# RemovingGround.net
KiCad netlist of a schematic drawn in EAGLE
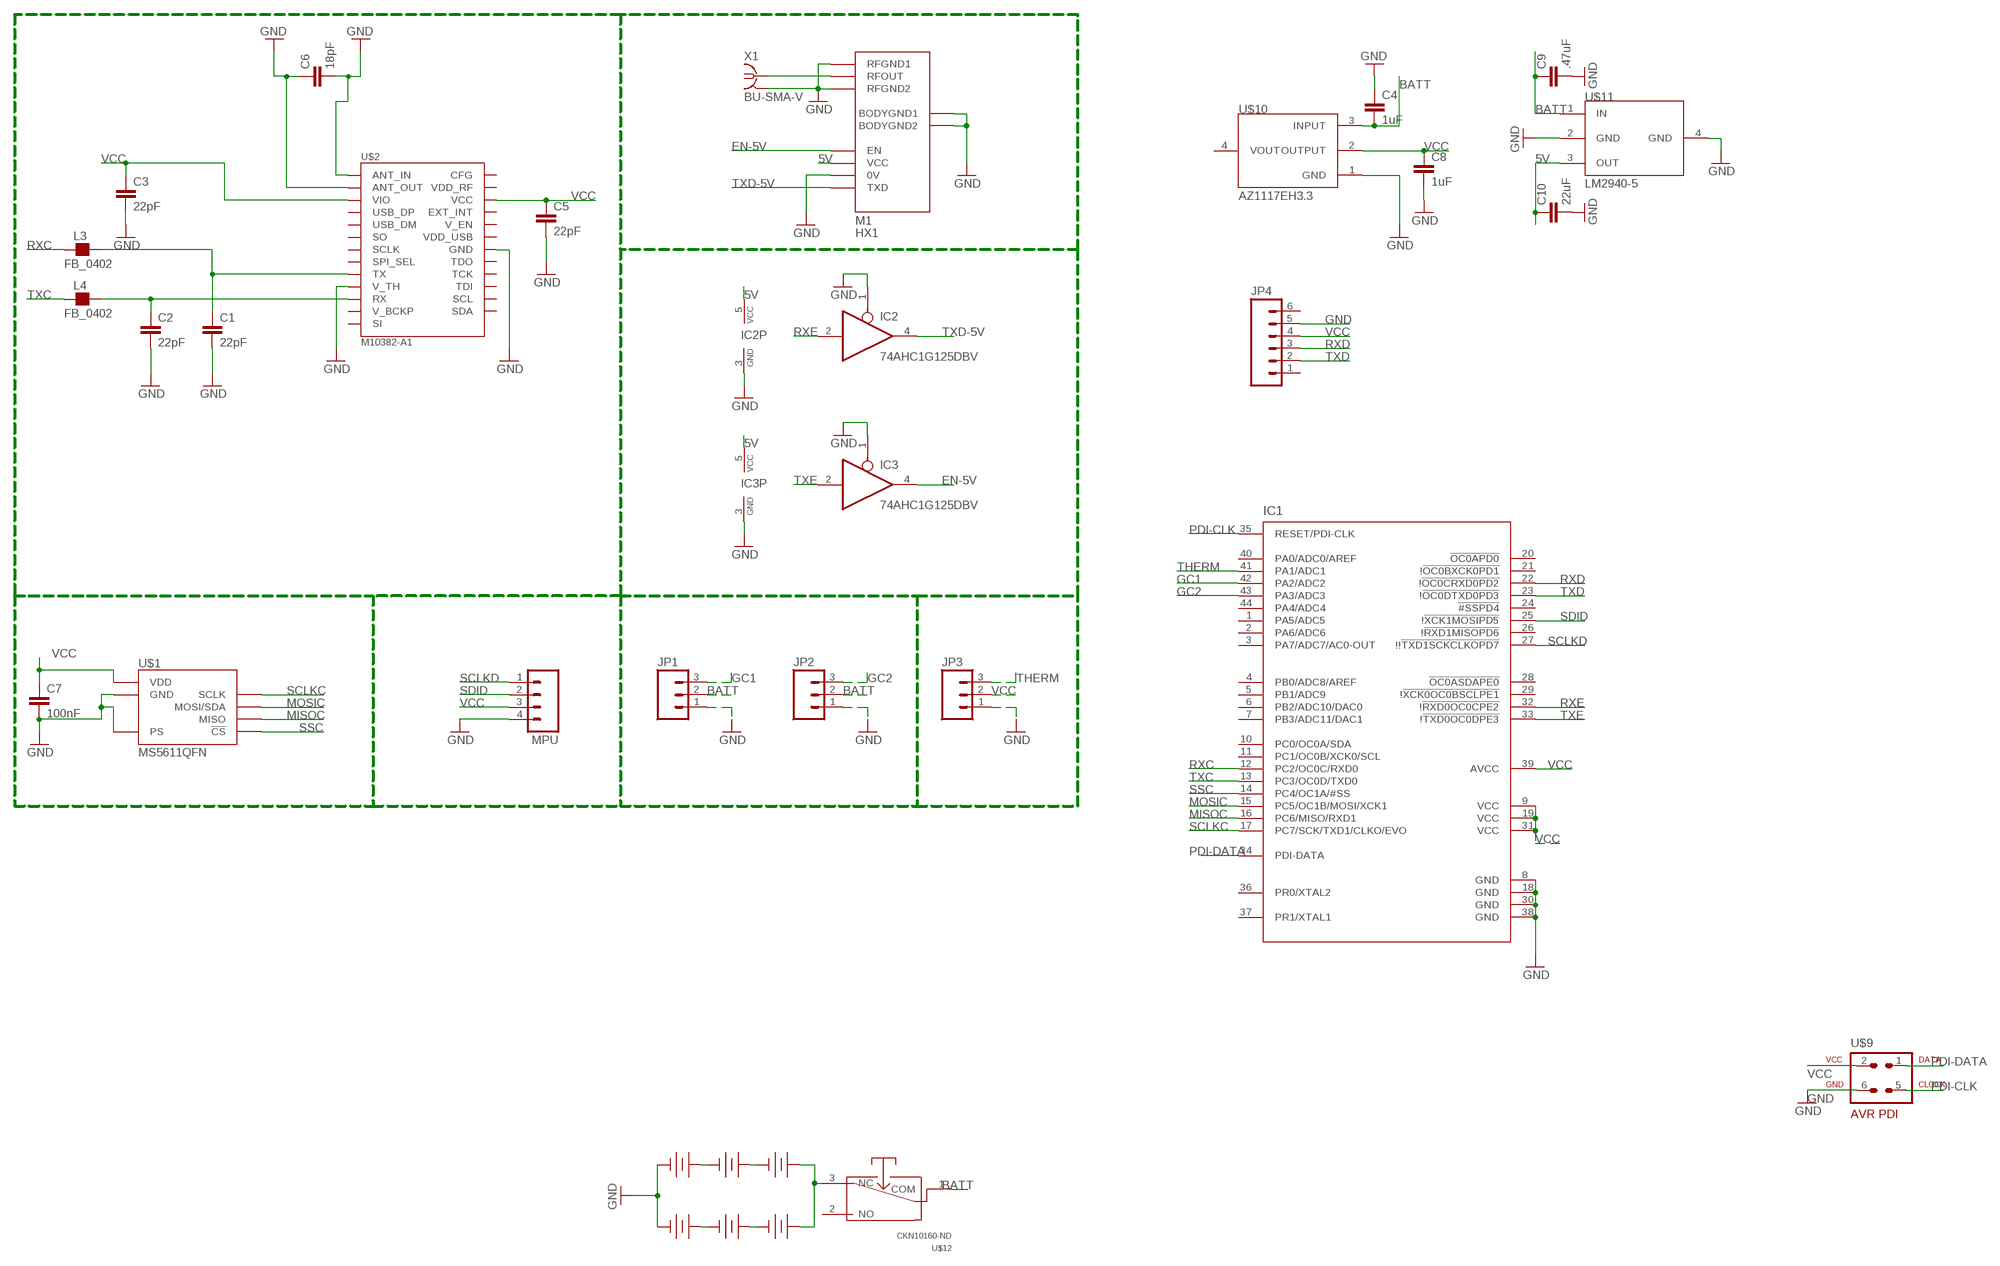
[diagram p0: schematic, sheet 1]

(export (version "E")
  (design (tool "Eeschema 10.0.6"))
  (components
    (comp (ref "C1")
      (value "22pF")
      (footprint "eagle-import:0805")
      (libsource (lib "eagle-import") (part "CAP0805"))
    )
    (comp (ref "C2")
      (value "22pF")
      (footprint "eagle-import:0805")
      (libsource (lib "eagle-import") (part "CAP0805"))
    )
    (comp (ref "C3")
      (value "22pF")
      (footprint "eagle-import:0805")
      (libsource (lib "eagle-import") (part "CAP0805"))
    )
    (comp (ref "C4")
      (value "1uF")
      (footprint "eagle-import:0603-CAP")
      (libsource (lib "eagle-import") (part "CAP0603-CAP"))
    )
    (comp (ref "C5")
      (value "22pF")
      (footprint "eagle-import:0805")
      (libsource (lib "eagle-import") (part "CAP0805"))
    )
    (comp (ref "C6")
      (value "18pF")
      (footprint "eagle-import:0805")
      (libsource (lib "eagle-import") (part "CAP0805"))
    )
    (comp (ref "C7")
      (value "100nF")
      (footprint "eagle-import:0805")
      (libsource (lib "eagle-import") (part "CAP0805"))
    )
    (comp (ref "C8")
      (value "1uF")
      (footprint "eagle-import:0603-CAP")
      (libsource (lib "eagle-import") (part "CAP0603-CAP"))
    )
    (comp (ref "C9")
      (value ".47uF")
      (footprint "eagle-import:0603-CAP")
      (libsource (lib "eagle-import") (part "CAP0603-CAP"))
    )
    (comp (ref "C10")
      (value "22uF")
      (footprint "eagle-import:0603-CAP")
      (libsource (lib "eagle-import") (part "CAP0603-CAP"))
    )
    (comp (ref "IC1")
      (value "AT-XMEGA-XXA4-AU")
      (footprint "eagle-import:QFP80P1200X1200X120-44N")
      (libsource (lib "eagle-import") (part "AT-XMEGA-XXA4-AU"))
    )
    (comp (ref "IC2")
      (value "74AHC1G125DBV")
      (footprint "eagle-import:SOT23-5")
      (libsource (lib "eagle-import") (part "741G125DBVAHC"))
    )
    (comp (ref "IC3")
      (value "74AHC1G125DBV")
      (footprint "eagle-import:SOT23-5")
      (libsource (lib "eagle-import") (part "741G125DBVAHC"))
    )
    (comp (ref "JP1")
      (value "M03JST-PTH")
      (footprint "eagle-import:JST-3-PTH")
      (libsource (lib "eagle-import") (part "M03JST-PTH"))
    )
    (comp (ref "JP2")
      (value "M03JST-PTH")
      (footprint "eagle-import:JST-3-PTH")
      (libsource (lib "eagle-import") (part "M03JST-PTH"))
    )
    (comp (ref "JP3")
      (value "M03JST-PTH")
      (footprint "eagle-import:JST-3-PTH")
      (libsource (lib "eagle-import") (part "M03JST-PTH"))
    )
    (comp (ref "JP4")
      (value "M06POLAR")
      (footprint "eagle-import:MOLEX-1X6")
      (libsource (lib "eagle-import") (part "M06POLAR"))
    )
    (comp (ref "L3")
      (value "FB_0402")
      (footprint "eagle-import:L0402")
      (libsource (lib "eagle-import") (part "FB_0402"))
    )
    (comp (ref "L4")
      (value "FB_0402")
      (footprint "eagle-import:L0402")
      (libsource (lib "eagle-import") (part "FB_0402"))
    )
    (comp (ref "M1")
      (value "HX1")
      (footprint "eagle-import:HX1")
      (libsource (lib "eagle-import") (part "HX1"))
    )
    (comp (ref "MPU")
      (value "M04")
      (footprint "eagle-import:04P")
      (libsource (lib "eagle-import") (part "M04"))
    )
    (comp (ref "U$1")
      (value "MS5611QFN")
      (footprint "eagle-import:MS5611-01BA01")
      (libsource (lib "eagle-import") (part "MS5611QFN"))
    )
    (comp (ref "U$2")
      (value "M10382-A1")
      (footprint "eagle-import:M10382-A1")
      (libsource (lib "eagle-import") (part "M10382-A1"))
    )
    (comp (ref "U$3")
      (value "123_BATTERY_HOLDERCR-123-A")
      (footprint "eagle-import:CR-123-A_HOLDER")
      (libsource (lib "eagle-import") (part "123_BATTERY_HOLDERCR-123-A"))
    )
    (comp (ref "U$4")
      (value "123_BATTERY_HOLDERCR-123-A")
      (footprint "eagle-import:CR-123-A_HOLDER")
      (libsource (lib "eagle-import") (part "123_BATTERY_HOLDERCR-123-A"))
    )
    (comp (ref "U$5")
      (value "123_BATTERY_HOLDERCR-123-A")
      (footprint "eagle-import:CR-123-A_HOLDER")
      (libsource (lib "eagle-import") (part "123_BATTERY_HOLDERCR-123-A"))
    )
    (comp (ref "U$6")
      (value "123_BATTERY_HOLDERCR-123-A")
      (footprint "eagle-import:CR-123-A_HOLDER")
      (libsource (lib "eagle-import") (part "123_BATTERY_HOLDERCR-123-A"))
    )
    (comp (ref "U$7")
      (value "123_BATTERY_HOLDERCR-123-A")
      (footprint "eagle-import:CR-123-A_HOLDER")
      (libsource (lib "eagle-import") (part "123_BATTERY_HOLDERCR-123-A"))
    )
    (comp (ref "U$8")
      (value "123_BATTERY_HOLDERCR-123-A")
      (footprint "eagle-import:CR-123-A_HOLDER")
      (libsource (lib "eagle-import") (part "123_BATTERY_HOLDERCR-123-A"))
    )
    (comp (ref "U$9")
      (value "AVR-PDIVERT")
      (footprint "eagle-import:AVR-ISP-6")
      (libsource (lib "eagle-import") (part "AVR-PDIVERT"))
    )
    (comp (ref "U$10")
      (value "AZ1117EH3.3")
      (footprint "eagle-import:SOT-223")
      (libsource (lib "eagle-import") (part "AZ1117EH3.3"))
    )
    (comp (ref "U$11")
      (value "LM2940-5")
      (footprint "eagle-import:SOT-223")
      (libsource (lib "eagle-import") (part "LM2940-5"))
    )
    (comp (ref "U$12")
      (value "CKN10160-ND")
      (footprint "eagle-import:ZMCHFL3R")
      (libsource (lib "eagle-import") (part "CKN10160-ND"))
    )
    (comp (ref "X1")
      (value "BU-SMA-V")
      (footprint "eagle-import:BU-SMA-V")
      (libsource (lib "eagle-import") (part "BU-SMA-V"))
    )
  )
  (nets
    (net (code "1") (name "/5V") (class "Default")
      (node (ref "C10") (pin "1") (pinfunction "1_1") (pintype "passive"))
      (node (ref "IC2") (pin "5") (pinfunction "VCC_5") (pintype "power_in"))
      (node (ref "IC3") (pin "5") (pinfunction "VCC_5") (pintype "power_in"))
      (node (ref "M1") (pin "VCC") (pinfunction "VCC_VCC") (pintype "bidirectional"))
      (node (ref "U$11") (pin "3") (pinfunction "OUT_3") (pintype "bidirectional"))
    )
    (net (code "2") (name "/BATT") (class "Default")
      (node (ref "C4") (pin "2") (pinfunction "2_2") (pintype "passive"))
      (node (ref "C9") (pin "1") (pinfunction "1_1") (pintype "passive"))
      (node (ref "JP1") (pin "2") (pinfunction "2_2") (pintype "passive"))
      (node (ref "JP2") (pin "2") (pinfunction "2_2") (pintype "passive"))
      (node (ref "U$10") (pin "3") (pinfunction "INPUT_3") (pintype "bidirectional"))
      (node (ref "U$11") (pin "1") (pinfunction "IN_1") (pintype "bidirectional"))
      (node (ref "U$12") (pin "1") (pinfunction "COM_1") (pintype "bidirectional"))
    )
    (net (code "3") (name "/EN-5V") (class "Default")
      (node (ref "IC3") (pin "4") (pinfunction "O_4") (pintype "tri_state"))
      (node (ref "M1") (pin "EN") (pinfunction "EN_EN") (pintype "bidirectional"))
    )
    (net (code "4") (name "/GC1") (class "Default")
      (node (ref "IC1") (pin "42") (pinfunction "PA2/ADC2_42") (pintype "bidirectional"))
      (node (ref "JP1") (pin "3") (pinfunction "3_3") (pintype "passive"))
    )
    (net (code "5") (name "/GC2") (class "Default")
      (node (ref "IC1") (pin "43") (pinfunction "PA3/ADC3_43") (pintype "bidirectional"))
      (node (ref "JP2") (pin "3") (pinfunction "3_3") (pintype "passive"))
    )
    (net (code "6") (name "/MISOC") (class "Default")
      (node (ref "IC1") (pin "16") (pinfunction "PC6/MISO/RXD1_16") (pintype "bidirectional"))
      (node (ref "U$1") (pin "6") (pinfunction "MISO_6") (pintype "bidirectional"))
    )
    (net (code "7") (name "/MOSIC") (class "Default")
      (node (ref "IC1") (pin "15") (pinfunction "PC5/OC1B/MOSI/XCK1_15") (pintype "bidirectional"))
      (node (ref "U$1") (pin "7") (pinfunction "MOSI/SDA_7") (pintype "bidirectional"))
    )
    (net (code "8") (name "/PDI-CLK") (class "Default")
      (node (ref "IC1") (pin "35") (pinfunction "RESET/PDI-CLK_35") (pintype "input"))
      (node (ref "U$9") (pin "5") (pinfunction "5_5") (pintype "passive"))
    )
    (net (code "9") (name "/PDI-DATA") (class "Default")
      (node (ref "IC1") (pin "34") (pinfunction "PDI-DATA_34") (pintype "bidirectional"))
      (node (ref "U$9") (pin "1") (pinfunction "1_1") (pintype "passive"))
    )
    (net (code "10") (name "/RXC") (class "Default")
      (node (ref "IC1") (pin "12") (pinfunction "PC2/OC0C/RXD0_12") (pintype "bidirectional"))
      (node (ref "L3") (pin "1") (pinfunction "1_1") (pintype "passive"))
    )
    (net (code "11") (name "/RXD") (class "Default")
      (node (ref "IC1") (pin "22") (pinfunction "~OC0CRXD0PD2_22") (pintype "bidirectional"))
      (node (ref "JP4") (pin "3") (pinfunction "3_3") (pintype "passive"))
    )
    (net (code "12") (name "/RXE") (class "Default")
      (node (ref "IC1") (pin "32") (pinfunction "~RXD0OC0CPE2_32") (pintype "bidirectional"))
      (node (ref "IC2") (pin "2") (pinfunction "I_2") (pintype "input"))
    )
    (net (code "13") (name "/SCLKC") (class "Default")
      (node (ref "IC1") (pin "17") (pinfunction "PC7/SCK/TXD1/CLKO/EVO_17") (pintype "bidirectional"))
      (node (ref "U$1") (pin "8") (pinfunction "SCLK_8") (pintype "bidirectional"))
    )
    (net (code "14") (name "/SCLKD") (class "Default")
      (node (ref "IC1") (pin "27") (pinfunction "~~{TXD1SCKCLKOPD7}_27") (pintype "bidirectional"))
      (node (ref "MPU") (pin "1") (pinfunction "1_1") (pintype "passive"))
    )
    (net (code "15") (name "/SDID") (class "Default")
      (node (ref "IC1") (pin "25") (pinfunction "~XCK1MOSIPD5_25") (pintype "bidirectional"))
      (node (ref "MPU") (pin "2") (pinfunction "2_2") (pintype "passive"))
    )
    (net (code "16") (name "/SSC") (class "Default")
      (node (ref "IC1") (pin "14") (pinfunction "PC4/OC1A/#SS_14") (pintype "bidirectional"))
      (node (ref "U$1") (pin "4") (pinfunction "~{CS}_4") (pintype "bidirectional"))
      (node (ref "U$1") (pin "5") (pinfunction "~{CS}_5") (pintype "bidirectional"))
    )
    (net (code "17") (name "/THERM") (class "Default")
      (node (ref "IC1") (pin "41") (pinfunction "PA1/ADC1_41") (pintype "bidirectional"))
      (node (ref "JP3") (pin "3") (pinfunction "3_3") (pintype "passive"))
    )
    (net (code "18") (name "/TXC") (class "Default")
      (node (ref "IC1") (pin "13") (pinfunction "PC3/OC0D/TXD0_13") (pintype "bidirectional"))
      (node (ref "L4") (pin "1") (pinfunction "1_1") (pintype "passive"))
    )
    (net (code "19") (name "/TXD") (class "Default")
      (node (ref "IC1") (pin "23") (pinfunction "~OC0DTXD0PD3_23") (pintype "bidirectional"))
      (node (ref "JP4") (pin "2") (pinfunction "2_2") (pintype "passive"))
    )
    (net (code "20") (name "/TXD-5V") (class "Default")
      (node (ref "IC2") (pin "4") (pinfunction "O_4") (pintype "tri_state"))
      (node (ref "M1") (pin "TXD") (pinfunction "TXD_TXD") (pintype "bidirectional"))
    )
    (net (code "21") (name "/TXE") (class "Default")
      (node (ref "IC1") (pin "33") (pinfunction "~TXD0OC0DPE3_33") (pintype "bidirectional"))
      (node (ref "IC3") (pin "2") (pinfunction "I_2") (pintype "input"))
    )
    (net (code "22") (name "/VCC") (class "Default")
      (node (ref "C3") (pin "1") (pinfunction "1_1") (pintype "passive"))
      (node (ref "C5") (pin "1") (pinfunction "1_1") (pintype "passive"))
      (node (ref "C7") (pin "1") (pinfunction "1_1") (pintype "passive"))
      (node (ref "C8") (pin "1") (pinfunction "1_1") (pintype "passive"))
      (node (ref "IC1") (pin "19") (pinfunction "VCC_19") (pintype "power_in"))
      (node (ref "IC1") (pin "31") (pinfunction "VCC_31") (pintype "power_in"))
      (node (ref "IC1") (pin "39") (pinfunction "AVCC_39") (pintype "power_in"))
      (node (ref "IC1") (pin "9") (pinfunction "VCC_9") (pintype "power_in"))
      (node (ref "JP3") (pin "2") (pinfunction "2_2") (pintype "passive"))
      (node (ref "JP4") (pin "4") (pinfunction "4_4") (pintype "passive"))
      (node (ref "MPU") (pin "3") (pinfunction "3_3") (pintype "passive"))
      (node (ref "U$1") (pin "1") (pinfunction "VDD_1") (pintype "bidirectional"))
      (node (ref "U$10") (pin "2") (pinfunction "OUTPUT_2") (pintype "bidirectional"))
      (node (ref "U$2") (pin "27") (pinfunction "VCC_27") (pintype "bidirectional"))
      (node (ref "U$2") (pin "5") (pinfunction "VIO_5") (pintype "bidirectional"))
      (node (ref "U$9") (pin "2") (pinfunction "2_2") (pintype "passive"))
    )
    (net (code "23") (name "GND") (class "Default")
      (node (ref "C1") (pin "2") (pinfunction "2_2") (pintype "passive"))
      (node (ref "C10") (pin "2") (pinfunction "2_2") (pintype "passive"))
      (node (ref "C2") (pin "2") (pinfunction "2_2") (pintype "passive"))
      (node (ref "C3") (pin "2") (pinfunction "2_2") (pintype "passive"))
      (node (ref "C4") (pin "1") (pinfunction "1_1") (pintype "passive"))
      (node (ref "C5") (pin "2") (pinfunction "2_2") (pintype "passive"))
      (node (ref "C6") (pin "1") (pinfunction "1_1") (pintype "passive"))
      (node (ref "C6") (pin "2") (pinfunction "2_2") (pintype "passive"))
      (node (ref "C7") (pin "2") (pinfunction "2_2") (pintype "passive"))
      (node (ref "C8") (pin "2") (pinfunction "2_2") (pintype "passive"))
      (node (ref "C9") (pin "2") (pinfunction "2_2") (pintype "passive"))
      (node (ref "IC1") (pin "18") (pinfunction "GND_18") (pintype "power_in"))
      (node (ref "IC1") (pin "30") (pinfunction "GND_30") (pintype "power_in"))
      (node (ref "IC1") (pin "38") (pinfunction "GND_38") (pintype "power_in"))
      (node (ref "IC1") (pin "8") (pinfunction "GND_8") (pintype "power_in"))
      (node (ref "IC2") (pin "1") (pinfunction "OE_1") (pintype "input"))
      (node (ref "IC2") (pin "3") (pinfunction "GND_3") (pintype "power_in"))
      (node (ref "IC3") (pin "1") (pinfunction "OE_1") (pintype "input"))
      (node (ref "IC3") (pin "3") (pinfunction "GND_3") (pintype "power_in"))
      (node (ref "JP1") (pin "1") (pinfunction "1_1") (pintype "passive"))
      (node (ref "JP2") (pin "1") (pinfunction "1_1") (pintype "passive"))
      (node (ref "JP3") (pin "1") (pinfunction "1_1") (pintype "passive"))
      (node (ref "JP4") (pin "5") (pinfunction "5_5") (pintype "passive"))
      (node (ref "M1") (pin "0V") (pinfunction "0V_0V") (pintype "bidirectional"))
      (node (ref "M1") (pin "BODYGND1") (pinfunction "BODYGND1_BODYGND1") (pintype "bidirectional"))
      (node (ref "M1") (pin "BODYGND2") (pinfunction "BODYGND2_BODYGND2") (pintype "bidirectional"))
      (node (ref "M1") (pin "RFGND1") (pinfunction "RFGND1_RFGND1") (pintype "bidirectional"))
      (node (ref "M1") (pin "RFGND2") (pinfunction "RFGND2_RFGND2") (pintype "bidirectional"))
      (node (ref "MPU") (pin "4") (pinfunction "4_4") (pintype "passive"))
      (node (ref "U$1") (pin "2") (pinfunction "PS_2") (pintype "bidirectional"))
      (node (ref "U$1") (pin "3") (pinfunction "GND_3") (pintype "bidirectional"))
      (node (ref "U$10") (pin "1") (pinfunction "GND_1") (pintype "bidirectional"))
      (node (ref "U$11") (pin "2") (pinfunction "GND_2") (pintype "bidirectional"))
      (node (ref "U$11") (pin "4") (pinfunction "GND_4") (pintype "bidirectional"))
      (node (ref "U$2") (pin "1") (pinfunction "ANT_IN_1") (pintype "bidirectional"))
      (node (ref "U$2") (pin "12") (pinfunction "V_TH_12") (pintype "bidirectional"))
      (node (ref "U$2") (pin "14") (pinfunction "GND_14") (pintype "bidirectional"))
      (node (ref "U$2") (pin "17") (pinfunction "GND_17") (pintype "bidirectional"))
      (node (ref "U$2") (pin "2") (pinfunction "GND_2") (pintype "bidirectional"))
      (node (ref "U$2") (pin "21") (pinfunction "GND_21") (pintype "bidirectional"))
      (node (ref "U$2") (pin "24") (pinfunction "GND_24") (pintype "bidirectional"))
      (node (ref "U$2") (pin "26") (pinfunction "GND_26") (pintype "bidirectional"))
      (node (ref "U$2") (pin "28") (pinfunction "GND_28") (pintype "bidirectional"))
      (node (ref "U$2") (pin "3") (pinfunction "ANT_OUT_3") (pintype "bidirectional"))
      (node (ref "U$2") (pin "33") (pinfunction "GND_33") (pintype "bidirectional"))
      (node (ref "U$2") (pin "34") (pinfunction "GND_34") (pintype "bidirectional"))
      (node (ref "U$2") (pin "35") (pinfunction "GND_35") (pintype "bidirectional"))
      (node (ref "U$2") (pin "36") (pinfunction "GND_36") (pintype "bidirectional"))
      (node (ref "U$2") (pin "4") (pinfunction "GND_4") (pintype "bidirectional"))
      (node (ref "U$3") (pin "-") (pinfunction "-_-") (pintype "bidirectional"))
      (node (ref "U$6") (pin "-") (pinfunction "-_-") (pintype "bidirectional"))
      (node (ref "U$9") (pin "6") (pinfunction "6_6") (pintype "passive"))
      (node (ref "X1") (pin "2") (pinfunction "GND_2") (pintype "power_in"))
    )
    (net (code "24") (name "Net-(M1-PadRFOUT)") (class "Default")
      (node (ref "M1") (pin "RFOUT") (pinfunction "RFOUT_RFOUT") (pintype "bidirectional"))
      (node (ref "X1") (pin "1") (pinfunction "1_1") (pintype "passive"))
    )
    (net (code "25") (name "Net-(U$2-RX)") (class "Default")
      (node (ref "C2") (pin "1") (pinfunction "1_1") (pintype "passive"))
      (node (ref "L4") (pin "2") (pinfunction "2_2") (pintype "passive"))
      (node (ref "U$2") (pin "13") (pinfunction "RX_13") (pintype "bidirectional"))
    )
    (net (code "26") (name "Net-(U$2-TX)") (class "Default")
      (node (ref "C1") (pin "1") (pinfunction "1_1") (pintype "passive"))
      (node (ref "L3") (pin "2") (pinfunction "2_2") (pintype "passive"))
      (node (ref "U$2") (pin "11") (pinfunction "TX_11") (pintype "bidirectional"))
    )
    (net (code "27") (name "Net-(U$3-Pad+)") (class "Default")
      (node (ref "U$3") (pin "+") (pinfunction "+_+") (pintype "bidirectional"))
      (node (ref "U$4") (pin "-") (pinfunction "-_-") (pintype "bidirectional"))
    )
    (net (code "28") (name "Net-(U$4-Pad+)") (class "Default")
      (node (ref "U$4") (pin "+") (pinfunction "+_+") (pintype "bidirectional"))
      (node (ref "U$5") (pin "-") (pinfunction "-_-") (pintype "bidirectional"))
    )
    (net (code "29") (name "Net-(U$6-Pad+)") (class "Default")
      (node (ref "U$6") (pin "+") (pinfunction "+_+") (pintype "bidirectional"))
      (node (ref "U$7") (pin "-") (pinfunction "-_-") (pintype "bidirectional"))
    )
    (net (code "30") (name "Net-(U$7-Pad+)") (class "Default")
      (node (ref "U$7") (pin "+") (pinfunction "+_+") (pintype "bidirectional"))
      (node (ref "U$8") (pin "-") (pinfunction "-_-") (pintype "bidirectional"))
    )
    (net (code "31") (name "Net-(U$12-NC)") (class "Default")
      (node (ref "U$12") (pin "3") (pinfunction "NC_3") (pintype "bidirectional"))
      (node (ref "U$5") (pin "+") (pinfunction "+_+") (pintype "bidirectional"))
      (node (ref "U$8") (pin "+") (pinfunction "+_+") (pintype "bidirectional"))
    )
    (net (code "32") (name "unconnected-(IC1-PA0{slash}ADC0{slash}AREF-Pad40)") (class "Default")
      (node (ref "IC1") (pin "40") (pinfunction "PA0/ADC0/AREF_40") (pintype "bidirectional"))
    )
    (net (code "33") (name "unconnected-(IC1-PA4{slash}ADC4-Pad44)") (class "Default")
      (node (ref "IC1") (pin "44") (pinfunction "PA4/ADC4_44") (pintype "bidirectional"))
    )
    (net (code "34") (name "unconnected-(IC1-PA5{slash}ADC5-Pad1)") (class "Default")
      (node (ref "IC1") (pin "1") (pinfunction "PA5/ADC5_1") (pintype "bidirectional"))
    )
    (net (code "35") (name "unconnected-(IC1-PA6{slash}ADC6-Pad2)") (class "Default")
      (node (ref "IC1") (pin "2") (pinfunction "PA6/ADC6_2") (pintype "bidirectional"))
    )
    (net (code "36") (name "unconnected-(IC1-PA7{slash}ADC7{slash}AC0-OUT-Pad3)") (class "Default")
      (node (ref "IC1") (pin "3") (pinfunction "PA7/ADC7/AC0-OUT_3") (pintype "bidirectional"))
    )
    (net (code "37") (name "unconnected-(IC1-PB0{slash}ADC8{slash}AREF-Pad4)") (class "Default")
      (node (ref "IC1") (pin "4") (pinfunction "PB0/ADC8/AREF_4") (pintype "bidirectional"))
    )
    (net (code "38") (name "unconnected-(IC1-PB1{slash}ADC9-Pad5)") (class "Default")
      (node (ref "IC1") (pin "5") (pinfunction "PB1/ADC9_5") (pintype "bidirectional"))
    )
    (net (code "39") (name "unconnected-(IC1-PB2{slash}ADC10{slash}DAC0-Pad6)") (class "Default")
      (node (ref "IC1") (pin "6") (pinfunction "PB2/ADC10/DAC0_6") (pintype "bidirectional"))
    )
    (net (code "40") (name "unconnected-(IC1-PB3{slash}ADC11{slash}DAC1-Pad7)") (class "Default")
      (node (ref "IC1") (pin "7") (pinfunction "PB3/ADC11/DAC1_7") (pintype "bidirectional"))
    )
    (net (code "41") (name "unconnected-(IC1-PC0{slash}OC0A{slash}SDA-Pad10)") (class "Default")
      (node (ref "IC1") (pin "10") (pinfunction "PC0/OC0A/SDA_10") (pintype "bidirectional"))
    )
    (net (code "42") (name "unconnected-(IC1-PC1{slash}OC0B{slash}XCK0{slash}SCL-Pad11)") (class "Default")
      (node (ref "IC1") (pin "11") (pinfunction "PC1/OC0B/XCK0/SCL_11") (pintype "bidirectional"))
    )
    (net (code "43") (name "unconnected-(IC1-PR0{slash}XTAL2-Pad36)") (class "Default")
      (node (ref "IC1") (pin "36") (pinfunction "PR0/XTAL2_36") (pintype "bidirectional"))
    )
    (net (code "44") (name "unconnected-(IC1-PR1{slash}XTAL1-Pad37)") (class "Default")
      (node (ref "IC1") (pin "37") (pinfunction "PR1/XTAL1_37") (pintype "bidirectional"))
    )
    (net (code "45") (name "unconnected-(IC1-~OC0BXCK0PD1-Pad21)") (class "Default")
      (node (ref "IC1") (pin "21") (pinfunction "~OC0BXCK0PD1_21") (pintype "bidirectional"))
    )
    (net (code "46") (name "unconnected-(IC1-~RXD1MISOPD6-Pad26)") (class "Default")
      (node (ref "IC1") (pin "26") (pinfunction "~RXD1MISOPD6_26") (pintype "bidirectional"))
    )
    (net (code "47") (name "unconnected-(IC1-~XCK0OC0BSCLPE1-Pad29)") (class "Default")
      (node (ref "IC1") (pin "29") (pinfunction "~XCK0OC0BSCLPE1_29") (pintype "bidirectional"))
    )
    (net (code "48") (name "unconnected-(IC1-~{#SSPD4}-Pad24)") (class "Default")
      (node (ref "IC1") (pin "24") (pinfunction "~{#SSPD4}_24") (pintype "bidirectional"))
    )
    (net (code "49") (name "unconnected-(IC1-~{OC0APD0}-Pad20)") (class "Default")
      (node (ref "IC1") (pin "20") (pinfunction "~{OC0APD0}_20") (pintype "bidirectional"))
    )
    (net (code "50") (name "unconnected-(IC1-~{OC0ASDAPE0}-Pad28)") (class "Default")
      (node (ref "IC1") (pin "28") (pinfunction "~{OC0ASDAPE0}_28") (pintype "bidirectional"))
    )
    (net (code "51") (name "unconnected-(JP4-Pad1)") (class "Default")
      (node (ref "JP4") (pin "1") (pinfunction "1_1") (pintype "passive"))
    )
    (net (code "52") (name "unconnected-(JP4-Pad6)") (class "Default")
      (node (ref "JP4") (pin "6") (pinfunction "6_6") (pintype "passive"))
    )
    (net (code "53") (name "unconnected-(U$2-CFG-Pad31)") (class "Default")
      (node (ref "U$2") (pin "31") (pinfunction "CFG_31") (pintype "bidirectional"))
    )
    (net (code "54") (name "unconnected-(U$2-EXT_INT-Pad29)") (class "Default")
      (node (ref "U$2") (pin "29") (pinfunction "EXT_INT_29") (pintype "bidirectional"))
    )
    (net (code "55") (name "unconnected-(U$2-SCL-Pad19)") (class "Default")
      (node (ref "U$2") (pin "19") (pinfunction "SCL_19") (pintype "bidirectional"))
    )
    (net (code "56") (name "unconnected-(U$2-SCLK-Pad9)") (class "Default")
      (node (ref "U$2") (pin "9") (pinfunction "SCLK_9") (pintype "bidirectional"))
    )
    (net (code "57") (name "unconnected-(U$2-SDA-Pad18)") (class "Default")
      (node (ref "U$2") (pin "18") (pinfunction "SDA_18") (pintype "bidirectional"))
    )
    (net (code "58") (name "unconnected-(U$2-SI-Pad16)") (class "Default")
      (node (ref "U$2") (pin "16") (pinfunction "SI_16") (pintype "bidirectional"))
    )
    (net (code "59") (name "unconnected-(U$2-SO-Pad8)") (class "Default")
      (node (ref "U$2") (pin "8") (pinfunction "SO_8") (pintype "bidirectional"))
    )
    (net (code "60") (name "unconnected-(U$2-SPI_SEL-Pad10)") (class "Default")
      (node (ref "U$2") (pin "10") (pinfunction "SPI_SEL_10") (pintype "bidirectional"))
    )
    (net (code "61") (name "unconnected-(U$2-TCK-Pad22)") (class "Default")
      (node (ref "U$2") (pin "22") (pinfunction "TCK_22") (pintype "bidirectional"))
    )
    (net (code "62") (name "unconnected-(U$2-TDI-Pad20)") (class "Default")
      (node (ref "U$2") (pin "20") (pinfunction "TDI_20") (pintype "bidirectional"))
    )
    (net (code "63") (name "unconnected-(U$2-TDO-Pad23)") (class "Default")
      (node (ref "U$2") (pin "23") (pinfunction "TDO_23") (pintype "bidirectional"))
    )
    (net (code "64") (name "unconnected-(U$2-USB_DM-Pad7)") (class "Default")
      (node (ref "U$2") (pin "7") (pinfunction "USB_DM_7") (pintype "bidirectional"))
    )
    (net (code "65") (name "unconnected-(U$2-USB_DP-Pad6)") (class "Default")
      (node (ref "U$2") (pin "6") (pinfunction "USB_DP_6") (pintype "bidirectional"))
    )
    (net (code "66") (name "unconnected-(U$2-VDD_RF-Pad25)") (class "Default")
      (node (ref "U$2") (pin "25") (pinfunction "VDD_RF_25") (pintype "bidirectional"))
    )
    (net (code "67") (name "unconnected-(U$2-VDD_USB-Pad32)") (class "Default")
      (node (ref "U$2") (pin "32") (pinfunction "VDD_USB_32") (pintype "bidirectional"))
    )
    (net (code "68") (name "unconnected-(U$2-V_BCKP-Pad15)") (class "Default")
      (node (ref "U$2") (pin "15") (pinfunction "V_BCKP_15") (pintype "bidirectional"))
    )
    (net (code "69") (name "unconnected-(U$2-V_EN-Pad30)") (class "Default")
      (node (ref "U$2") (pin "30") (pinfunction "V_EN_30") (pintype "bidirectional"))
    )
    (net (code "70") (name "unconnected-(U$10-VOUT-Pad4)") (class "Default")
      (node (ref "U$10") (pin "4") (pinfunction "VOUT_4") (pintype "bidirectional"))
    )
    (net (code "71") (name "unconnected-(U$12-NO-Pad2)") (class "Default")
      (node (ref "U$12") (pin "2") (pinfunction "NO_2") (pintype "bidirectional"))
    )
  )
)
